# SCH_SmartHealthMonitor_2021-09-16.net
KiCad netlist of a schematic drawn in EasyEDA
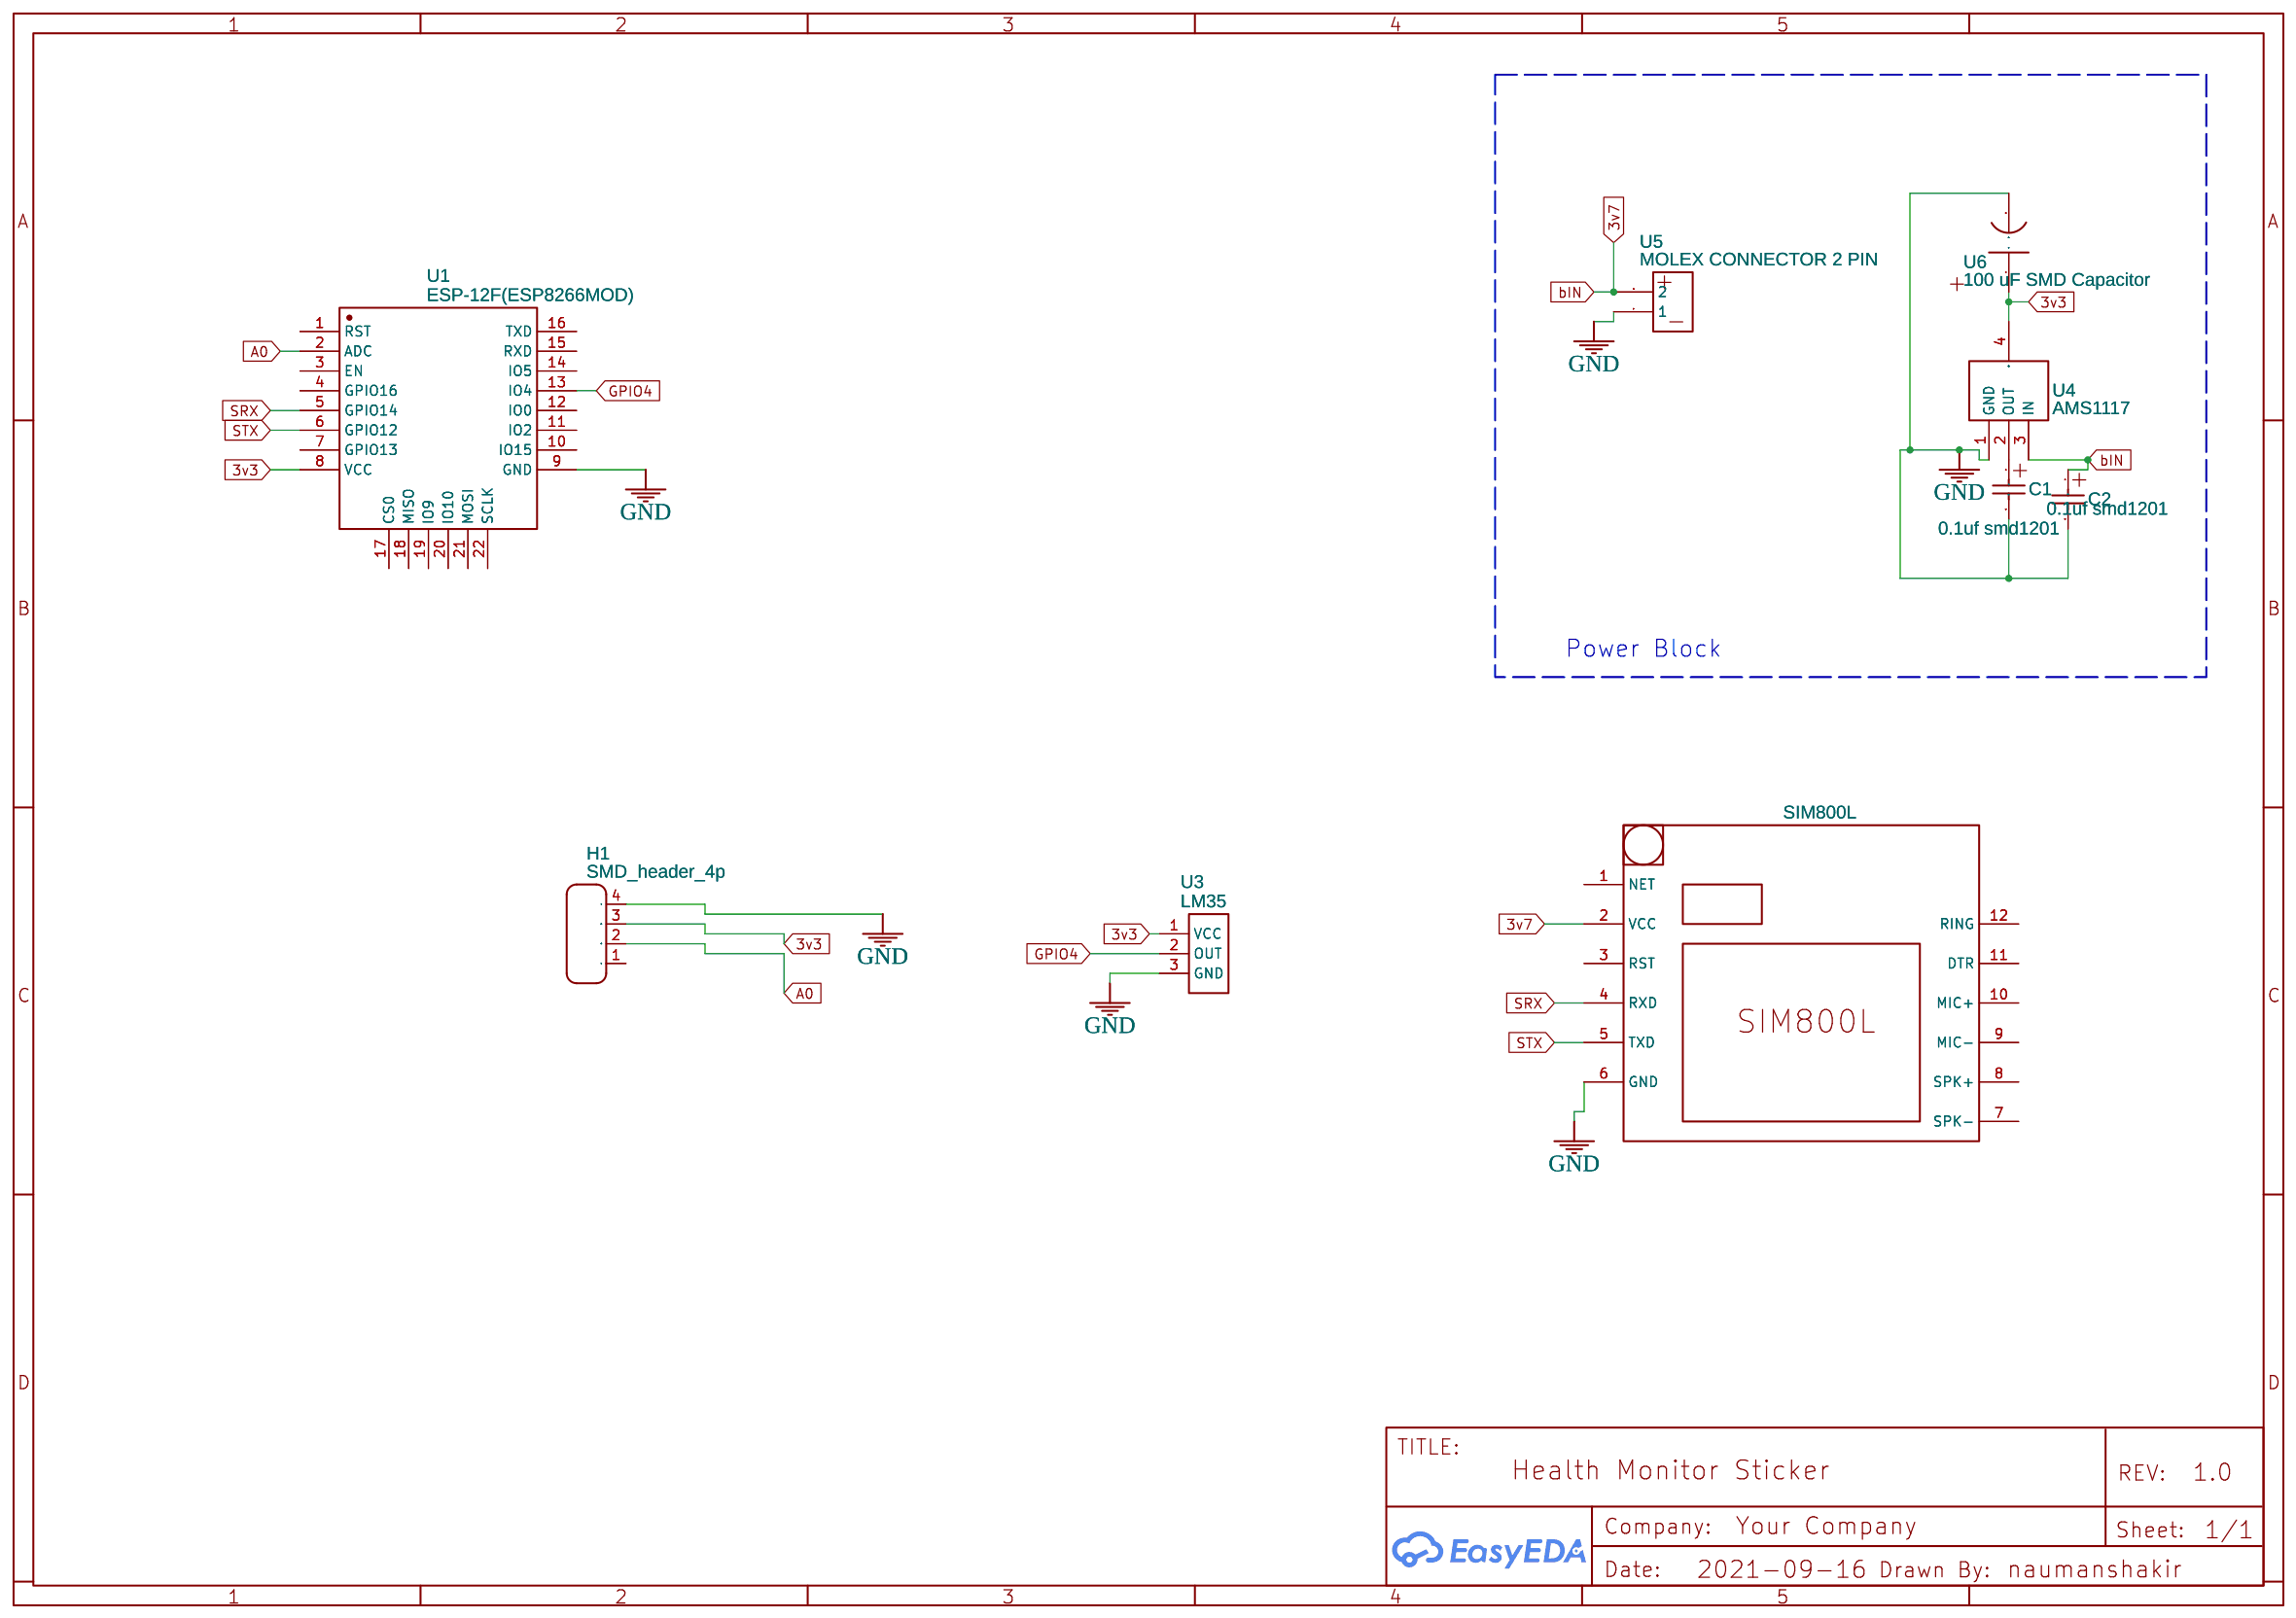
[diagram p0: schematic sheet]

(export (version "E")
  (design (tool "Eeschema 10.0.6"))
  (components
    (comp (ref "C1") (value "0.1uf smd1201") (libsource (lib "") (part "0.1uf smd1201_1")))
    (comp (ref "C2") (value "0.1uf smd1201") (libsource (lib "") (part "0.1uf smd1201")))
    (comp (ref "H1") (value "SMD_header_4p") (libsource (lib "") (part "SMD_header_4p")))
    (comp (ref "NET") (value "SIM800L") (libsource (lib "") (part "SIM800L")))
    (comp (ref "U1")
      (value "ESP-12F(ESP8266MOD)")
      (fields (field (name "BOM_Supplier Part") "C82891"))
      (libsource (lib "") (part "ESP-12F(ESP8266MOD)"))
    )
    (comp (ref "U3")
      (value "LM35")
      (fields (field (name "BOM_Supplier Part") "926-LM35DZ/NOPB"))
      (libsource (lib "") (part "LM35"))
    )
    (comp (ref "U4") (value "AMS1117") (libsource (lib "") (part "AMS1117")))
    (comp (ref "U5")
      (value "MOLEX CONNECTOR 2 PIN")
      (fields (field (name "BOM_Manufacturer Part") "MOLEX SMD CONNECTOR 2 PIN"))
      (libsource (lib "") (part "MOLEX CONNECTOR 2 PIN"))
    )
    (comp (ref "U6")
      (value "100 uF SMD Capacitor")
      (fields
        (field (name "BOM_Manufacturer Part") "JMK325ABJ107MM-T")
        (field (name "BOM_Supplier Part") "C92794")
      )
      (libsource (lib "") (part "100 uF SMD Capacitor"))
    )
  )
  (nets
    (net (code "1") (name "3v3") (class "Default")
      (node (ref "H1") (pin "3") (pinfunction "3_3") (pintype "unspecified"))
      (node (ref "U1") (pin "8") (pinfunction "VCC_8") (pintype "unspecified"))
      (node (ref "U3") (pin "1") (pinfunction "VCC_1") (pintype "unspecified"))
      (node (ref "U4") (pin "4") (pinfunction "GND_4") (pintype "unspecified"))
      (node (ref "U6") (pin "1") (pinfunction "1_1") (pintype "unspecified"))
    )
    (net (code "2") (name "3v7") (class "Default")
      (node (ref "C2") (pin "1") (pinfunction "1_1") (pintype "input"))
      (node (ref "NET") (pin "2") (pinfunction "VCC_2") (pintype "passive"))
      (node (ref "U4") (pin "3") (pinfunction "IN_3") (pintype "unspecified"))
      (node (ref "U5") (pin "2") (pinfunction "2_2") (pintype "unspecified"))
    )
    (net (code "3") (name "A0") (class "Default")
      (node (ref "H1") (pin "2") (pinfunction "2_2") (pintype "unspecified"))
      (node (ref "U1") (pin "2") (pinfunction "ADC_2") (pintype "unspecified"))
    )
    (net (code "4") (name "GND") (class "Default")
      (node (ref "C1") (pin "2") (pinfunction "2_2") (pintype "input"))
      (node (ref "C2") (pin "2") (pinfunction "2_2") (pintype "input"))
      (node (ref "H1") (pin "4") (pinfunction "4_4") (pintype "unspecified"))
      (node (ref "NET") (pin "6") (pinfunction "GND_6") (pintype "unspecified"))
      (node (ref "U1") (pin "9") (pinfunction "GND_9") (pintype "unspecified"))
      (node (ref "U3") (pin "3") (pinfunction "GND_3") (pintype "unspecified"))
      (node (ref "U4") (pin "1") (pinfunction "GND_1") (pintype "unspecified"))
      (node (ref "U5") (pin "1") (pinfunction "1_1") (pintype "unspecified"))
      (node (ref "U6") (pin "2") (pinfunction "2_2") (pintype "unspecified"))
    )
    (net (code "5") (name "GPIO4") (class "Default")
      (node (ref "U1") (pin "13") (pinfunction "IO4_13") (pintype "unspecified"))
      (node (ref "U3") (pin "2") (pinfunction "OUT_2") (pintype "unspecified"))
    )
    (net (code "6") (name "Net-(U4-OUT)") (class "Default")
      (node (ref "C1") (pin "1") (pinfunction "1_1") (pintype "input"))
      (node (ref "U4") (pin "2") (pinfunction "OUT_2") (pintype "unspecified"))
    )
    (net (code "7") (name "SRX") (class "Default")
      (node (ref "NET") (pin "4") (pinfunction "RXD_4") (pintype "unspecified"))
      (node (ref "U1") (pin "5") (pinfunction "GPIO14_5") (pintype "unspecified"))
    )
    (net (code "8") (name "STX") (class "Default")
      (node (ref "NET") (pin "5") (pinfunction "TXD_5") (pintype "unspecified"))
      (node (ref "U1") (pin "6") (pinfunction "GPIO12_6") (pintype "unspecified"))
    )
    (net (code "9") (name "unconnected-(H1-Pad1)") (class "Default")
      (node (ref "H1") (pin "1") (pinfunction "1_1") (pintype "unspecified"))
    )
    (net (code "10") (name "unconnected-(NET-DTR-Pad11)") (class "Default")
      (node (ref "NET") (pin "11") (pinfunction "DTR_11") (pintype "unspecified"))
    )
    (net (code "11") (name "unconnected-(NET-MIC+-Pad10)") (class "Default")
      (node (ref "NET") (pin "10") (pinfunction "MIC+_10") (pintype "unspecified"))
    )
    (net (code "12") (name "unconnected-(NET-MIC--Pad9)") (class "Default")
      (node (ref "NET") (pin "9") (pinfunction "MIC-_9") (pintype "unspecified"))
    )
    (net (code "13") (name "unconnected-(NET-NET-Pad1)") (class "Default")
      (node (ref "NET") (pin "1") (pinfunction "NET_1") (pintype "unspecified"))
    )
    (net (code "14") (name "unconnected-(NET-RING-Pad12)") (class "Default")
      (node (ref "NET") (pin "12") (pinfunction "RING_12") (pintype "unspecified"))
    )
    (net (code "15") (name "unconnected-(NET-RST-Pad3)") (class "Default")
      (node (ref "NET") (pin "3") (pinfunction "RST_3") (pintype "unspecified"))
    )
    (net (code "16") (name "unconnected-(NET-SPK+-Pad8)") (class "Default")
      (node (ref "NET") (pin "8") (pinfunction "SPK+_8") (pintype "unspecified"))
    )
    (net (code "17") (name "unconnected-(NET-SPK--Pad7)") (class "Default")
      (node (ref "NET") (pin "7") (pinfunction "SPK-_7") (pintype "unspecified"))
    )
    (net (code "18") (name "unconnected-(U1-CS0-Pad17)") (class "Default")
      (node (ref "U1") (pin "17") (pinfunction "CS0_17") (pintype "unspecified"))
    )
    (net (code "19") (name "unconnected-(U1-EN-Pad3)") (class "Default")
      (node (ref "U1") (pin "3") (pinfunction "EN_3") (pintype "unspecified"))
    )
    (net (code "20") (name "unconnected-(U1-GPIO13-Pad7)") (class "Default")
      (node (ref "U1") (pin "7") (pinfunction "GPIO13_7") (pintype "unspecified"))
    )
    (net (code "21") (name "unconnected-(U1-GPIO16-Pad4)") (class "Default")
      (node (ref "U1") (pin "4") (pinfunction "GPIO16_4") (pintype "unspecified"))
    )
    (net (code "22") (name "unconnected-(U1-IO0-Pad12)") (class "Default")
      (node (ref "U1") (pin "12") (pinfunction "IO0_12") (pintype "unspecified"))
    )
    (net (code "23") (name "unconnected-(U1-IO2-Pad11)") (class "Default")
      (node (ref "U1") (pin "11") (pinfunction "IO2_11") (pintype "unspecified"))
    )
    (net (code "24") (name "unconnected-(U1-IO5-Pad14)") (class "Default")
      (node (ref "U1") (pin "14") (pinfunction "IO5_14") (pintype "unspecified"))
    )
    (net (code "25") (name "unconnected-(U1-IO9-Pad19)") (class "Default")
      (node (ref "U1") (pin "19") (pinfunction "IO9_19") (pintype "unspecified"))
    )
    (net (code "26") (name "unconnected-(U1-IO10-Pad20)") (class "Default")
      (node (ref "U1") (pin "20") (pinfunction "IO10_20") (pintype "unspecified"))
    )
    (net (code "27") (name "unconnected-(U1-IO15-Pad10)") (class "Default")
      (node (ref "U1") (pin "10") (pinfunction "IO15_10") (pintype "unspecified"))
    )
    (net (code "28") (name "unconnected-(U1-MISO-Pad18)") (class "Default")
      (node (ref "U1") (pin "18") (pinfunction "MISO_18") (pintype "unspecified"))
    )
    (net (code "29") (name "unconnected-(U1-MOSI-Pad21)") (class "Default")
      (node (ref "U1") (pin "21") (pinfunction "MOSI_21") (pintype "unspecified"))
    )
    (net (code "30") (name "unconnected-(U1-RST-Pad1)") (class "Default")
      (node (ref "U1") (pin "1") (pinfunction "RST_1") (pintype "unspecified"))
    )
    (net (code "31") (name "unconnected-(U1-RXD-Pad15)") (class "Default")
      (node (ref "U1") (pin "15") (pinfunction "RXD_15") (pintype "unspecified"))
    )
    (net (code "32") (name "unconnected-(U1-SCLK-Pad22)") (class "Default")
      (node (ref "U1") (pin "22") (pinfunction "SCLK_22") (pintype "unspecified"))
    )
    (net (code "33") (name "unconnected-(U1-TXD-Pad16)") (class "Default")
      (node (ref "U1") (pin "16") (pinfunction "TXD_16") (pintype "unspecified"))
    )
  )
)
